# btmat.net
KiCad netlist of a schematic drawn in EAGLE
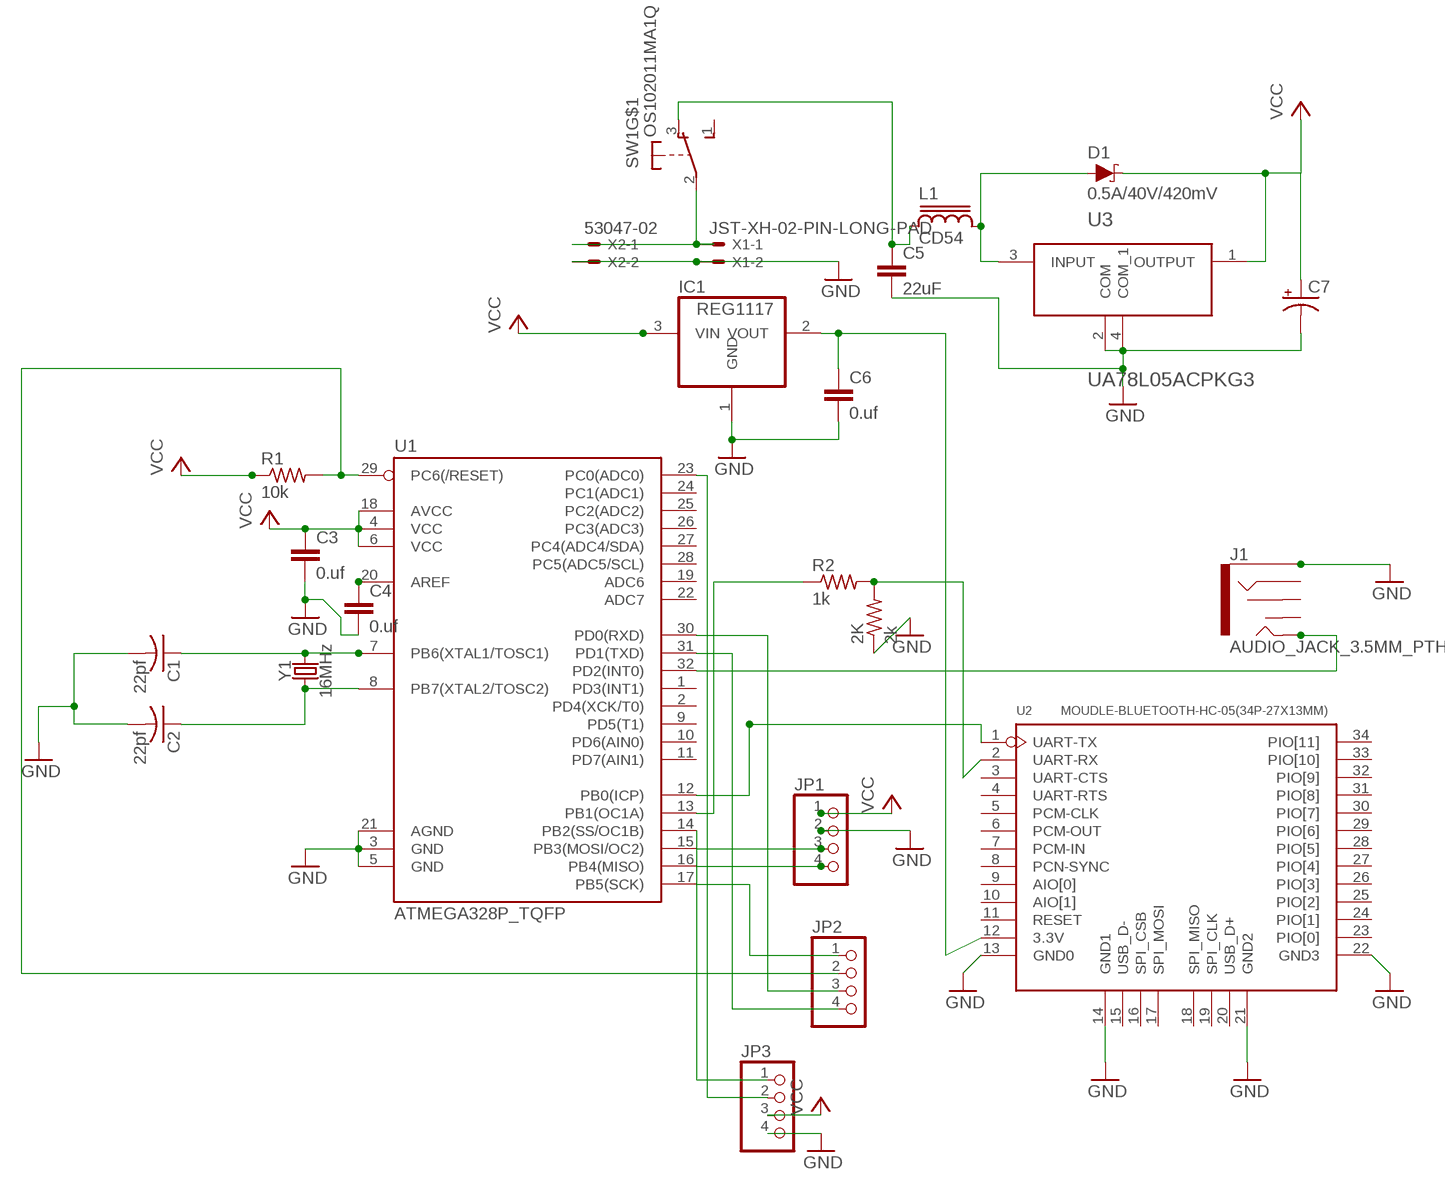
[diagram p0: schematic, sheet 1]

(export (version "E")
  (design (tool "Eeschema 10.0.6"))
  (components
    (comp (ref "2K")
      (value "2k")
      (footprint "eagle-import:R0805")
      (libsource (lib "eagle-import") (part "R-US_R0805"))
    )
    (comp (ref "C1")
      (value "22pf")
      (footprint "eagle-import:C0805")
      (libsource (lib "eagle-import") (part "C-USC0805"))
    )
    (comp (ref "C2")
      (value "22pf")
      (footprint "eagle-import:C0805")
      (libsource (lib "eagle-import") (part "C-USC0805"))
    )
    (comp (ref "C3")
      (value "0.uf")
      (footprint "eagle-import:C0805")
      (libsource (lib "eagle-import") (part "resistor_348_C-EUC0805"))
    )
    (comp (ref "C4")
      (value "0.uf")
      (footprint "eagle-import:C0805")
      (libsource (lib "eagle-import") (part "resistor_348_C-EUC0805"))
    )
    (comp (ref "C5")
      (value "22uF")
      (footprint "eagle-import:C0805")
      (libsource (lib "eagle-import") (part "C-EUC0805"))
    )
    (comp (ref "C6")
      (value "0.uf")
      (footprint "eagle-import:C0805")
      (libsource (lib "eagle-import") (part "resistor_348_C-EUC0805"))
    )
    (comp (ref "C7")
      (value "CPOL-USC/6032-28R")
      (footprint "eagle-import:C_6032-28R")
      (libsource (lib "eagle-import") (part "CPOL-USC/6032-28R"))
    )
    (comp (ref "D1")
      (value "0.5A/40V/420mV")
      (footprint "eagle-import:SOD-323")
      (libsource (lib "eagle-import") (part "DIODE-SCHOTTKY-PMEG4005EJ"))
    )
    (comp (ref "IC1")
      (value "REG1117")
      (footprint "eagle-import:SOT223")
      (libsource (lib "eagle-import") (part "REG1117"))
    )
    (comp (ref "J1")
      (value "AUDIO_JACK_3.5MM_PTH")
      (footprint "eagle-import:AUDIO-JACK")
      (libsource (lib "eagle-import") (part "AUDIO_JACK_3.5MM_PTH"))
    )
    (comp (ref "JP1")
      (value "PINHD-1X4")
      (footprint "eagle-import:1X04")
      (libsource (lib "eagle-import") (part "PINHD-1X4"))
    )
    (comp (ref "JP2")
      (value "PINHD-1X4")
      (footprint "eagle-import:1X04")
      (libsource (lib "eagle-import") (part "PINHD-1X4"))
    )
    (comp (ref "JP3")
      (value "PINHD-1X4")
      (footprint "eagle-import:1X04")
      (libsource (lib "eagle-import") (part "PINHD-1X4"))
    )
    (comp (ref "L1")
      (value "CD54")
      (footprint "eagle-import:CD54")
      (libsource (lib "eagle-import") (part "CD54"))
    )
    (comp (ref "R1")
      (value "10k")
      (footprint "eagle-import:R0805")
      (libsource (lib "eagle-import") (part "R-US_R0805"))
    )
    (comp (ref "R2")
      (value "1k")
      (footprint "eagle-import:R0805")
      (libsource (lib "eagle-import") (part "R-US_R0805"))
    )
    (comp (ref "SW1")
      (value "OS102011MA1Q")
      (footprint "eagle-import:OS102011MA1Q")
      (libsource (lib "eagle-import") (part "OS102011MA1Q"))
    )
    (comp (ref "U1")
      (value "ATMEGA328P_TQFP")
      (footprint "eagle-import:TQFP32-08")
      (libsource (lib "eagle-import") (part "ATMEGA328P_TQFP"))
    )
    (comp (ref "U2")
      (value "MOUDLE-BLUETOOTH-HC-05(34P-27X13MM)")
      (footprint "eagle-import:BT34P-SMD-1.5-26.9X13.0X2.2MM")
      (fields (field (name "MP") "HC-05"))
      (libsource (lib "eagle-import") (part "MOUDLE-BLUETOOTH-HC-05(34P-27X13MM)"))
    )
    (comp (ref "U3")
      (value "UA78L05ACPKG3")
      (footprint "eagle-import:SOT150P400X160-4N")
      (libsource (lib "eagle-import") (part "UA78L05ACPKG3"))
    )
    (comp (ref "X1")
      (value "JST-XH-02-PIN-LONG-PAD")
      (footprint "eagle-import:JST-XH-02-PACKAGE-LONG-PAD")
      (libsource (lib "eagle-import") (part "JST-XH-02-PIN-LONG-PAD"))
    )
    (comp (ref "X2")
      (value "53047-02")
      (footprint "eagle-import:53047-02")
      (fields (field (name "MF") "MOLEX") (field (name "MPN") "53047-0210"))
      (libsource (lib "eagle-import") (part "53?-02047"))
    )
    (comp (ref "Y1")
      (value "16MHz")
      (footprint "eagle-import:HC49US")
      (libsource (lib "eagle-import") (part "CRYSTAL-16MHZPTH-HC49US"))
    )
  )
  (nets
    (net (code "1") (name "GND") (class "Default")
      (node (ref "2K") (pin "1") (pinfunction "1_1") (pintype "passive"))
      (node (ref "C1") (pin "2") (pinfunction "2_2") (pintype "passive"))
      (node (ref "C2") (pin "2") (pinfunction "2_2") (pintype "passive"))
      (node (ref "C3") (pin "2") (pinfunction "2_2") (pintype "passive"))
      (node (ref "C4") (pin "2") (pinfunction "2_2") (pintype "passive"))
      (node (ref "C5") (pin "2") (pinfunction "2_2") (pintype "passive"))
      (node (ref "C6") (pin "2") (pinfunction "2_2") (pintype "passive"))
      (node (ref "C7") (pin "-") (pinfunction "-_-") (pintype "passive"))
      (node (ref "IC1") (pin "1") (pinfunction "GND_1") (pintype "power_in"))
      (node (ref "J1") (pin "SLEEVE") (pinfunction "SLEEVE_SLEEVE") (pintype "bidirectional"))
      (node (ref "JP1") (pin "2") (pinfunction "2_2") (pintype "passive"))
      (node (ref "JP3") (pin "4") (pinfunction "4_4") (pintype "passive"))
      (node (ref "U1") (pin "21") (pinfunction "AGND_21") (pintype "bidirectional"))
      (node (ref "U1") (pin "3") (pinfunction "GND_3") (pintype "bidirectional"))
      (node (ref "U1") (pin "5") (pinfunction "GND_5") (pintype "bidirectional"))
      (node (ref "U2") (pin "13") (pinfunction "GND0_13") (pintype "bidirectional"))
      (node (ref "U2") (pin "14") (pinfunction "GND1_14") (pintype "bidirectional"))
      (node (ref "U2") (pin "21") (pinfunction "GND2_21") (pintype "bidirectional"))
      (node (ref "U2") (pin "22") (pinfunction "GND3_22") (pintype "bidirectional"))
      (node (ref "U3") (pin "2") (pinfunction "COM_2") (pintype "power_in"))
      (node (ref "U3") (pin "4") (pinfunction "COM_1_4") (pintype "power_in"))
      (node (ref "X1") (pin "2") (pinfunction "S_2") (pintype "passive"))
      (node (ref "X2") (pin "2") (pinfunction "S_2") (pintype "passive"))
    )
    (net (code "2") (name "Net-(IC1-VOUT)") (class "Default")
      (node (ref "C6") (pin "1") (pinfunction "1_1") (pintype "passive"))
      (node (ref "IC1") (pin "2") (pinfunction "VOUT_2") (pintype "output"))
      (node (ref "U2") (pin "12") (pinfunction "3.3V_12") (pintype "bidirectional"))
    )
    (net (code "3") (name "Net-(SW1A-O)") (class "Default")
      (node (ref "C5") (pin "1") (pinfunction "1_1") (pintype "passive"))
      (node (ref "L1") (pin "1") (pinfunction "1_1") (pintype "passive"))
      (node (ref "SW1") (pin "3") (pinfunction "O_3") (pintype "passive"))
    )
    (net (code "4") (name "Net-(SW1A-P)") (class "Default")
      (node (ref "SW1") (pin "2") (pinfunction "P_2") (pintype "passive"))
      (node (ref "X1") (pin "1") (pinfunction "S_1") (pintype "passive"))
      (node (ref "X2") (pin "1") (pinfunction "S_1") (pintype "passive"))
    )
    (net (code "5") (name "Net-(U1-AREF)") (class "Default")
      (node (ref "C4") (pin "1") (pinfunction "1_1") (pintype "passive"))
      (node (ref "U1") (pin "20") (pinfunction "AREF_20") (pintype "bidirectional"))
    )
    (net (code "6") (name "Net-(U1-PB0(ICP))") (class "Default")
      (node (ref "U1") (pin "12") (pinfunction "PB0(ICP)_12") (pintype "bidirectional"))
      (node (ref "U2") (pin "1") (pinfunction "UART-TX_1") (pintype "bidirectional"))
    )
    (net (code "7") (name "Net-(U1-PB1(OC1A))") (class "Default")
      (node (ref "R2") (pin "1") (pinfunction "1_1") (pintype "passive"))
      (node (ref "U1") (pin "13") (pinfunction "PB1(OC1A)_13") (pintype "bidirectional"))
    )
    (net (code "8") (name "Net-(U1-PB2(SS{slash}OC1B))") (class "Default")
      (node (ref "JP3") (pin "1") (pinfunction "1_1") (pintype "passive"))
      (node (ref "U1") (pin "14") (pinfunction "PB2(SS/OC1B)_14") (pintype "bidirectional"))
    )
    (net (code "9") (name "Net-(U1-PB3(MOSI{slash}OC2))") (class "Default")
      (node (ref "JP1") (pin "3") (pinfunction "3_3") (pintype "passive"))
      (node (ref "U1") (pin "15") (pinfunction "PB3(MOSI/OC2)_15") (pintype "bidirectional"))
    )
    (net (code "10") (name "Net-(U1-PB4(MISO))") (class "Default")
      (node (ref "JP1") (pin "4") (pinfunction "4_4") (pintype "passive"))
      (node (ref "U1") (pin "16") (pinfunction "PB4(MISO)_16") (pintype "bidirectional"))
    )
    (net (code "11") (name "Net-(U1-PB5(SCK))") (class "Default")
      (node (ref "JP2") (pin "1") (pinfunction "1_1") (pintype "passive"))
      (node (ref "U1") (pin "17") (pinfunction "PB5(SCK)_17") (pintype "bidirectional"))
    )
    (net (code "12") (name "Net-(U1-PB6(XTAL1{slash}TOSC1))") (class "Default")
      (node (ref "C1") (pin "1") (pinfunction "1_1") (pintype "passive"))
      (node (ref "U1") (pin "7") (pinfunction "PB6(XTAL1/TOSC1)_7") (pintype "bidirectional"))
      (node (ref "Y1") (pin "2") (pinfunction "2_2") (pintype "passive"))
    )
    (net (code "13") (name "Net-(U1-PB7(XTAL2{slash}TOSC2))") (class "Default")
      (node (ref "C2") (pin "1") (pinfunction "1_1") (pintype "passive"))
      (node (ref "U1") (pin "8") (pinfunction "PB7(XTAL2/TOSC2)_8") (pintype "bidirectional"))
      (node (ref "Y1") (pin "1") (pinfunction "1_1") (pintype "passive"))
    )
    (net (code "14") (name "Net-(U1-PC0(ADC0))") (class "Default")
      (node (ref "JP3") (pin "2") (pinfunction "2_2") (pintype "passive"))
      (node (ref "U1") (pin "23") (pinfunction "PC0(ADC0)_23") (pintype "bidirectional"))
    )
    (net (code "15") (name "Net-(U1-PC6({slash}RESET))") (class "Default")
      (node (ref "JP2") (pin "2") (pinfunction "2_2") (pintype "passive"))
      (node (ref "R1") (pin "2") (pinfunction "2_2") (pintype "passive"))
      (node (ref "U1") (pin "29") (pinfunction "PC6(/RESET)_29") (pintype "bidirectional"))
    )
    (net (code "16") (name "Net-(U1-PD0(RXD))") (class "Default")
      (node (ref "JP2") (pin "3") (pinfunction "3_3") (pintype "passive"))
      (node (ref "U1") (pin "30") (pinfunction "PD0(RXD)_30") (pintype "bidirectional"))
    )
    (net (code "17") (name "Net-(U1-PD1(TXD))") (class "Default")
      (node (ref "JP2") (pin "4") (pinfunction "4_4") (pintype "passive"))
      (node (ref "U1") (pin "31") (pinfunction "PD1(TXD)_31") (pintype "bidirectional"))
    )
    (net (code "18") (name "Net-(U1-PD2(INT0))") (class "Default")
      (node (ref "J1") (pin "TIP") (pinfunction "TIP_TIP") (pintype "bidirectional"))
      (node (ref "U1") (pin "32") (pinfunction "PD2(INT0)_32") (pintype "bidirectional"))
    )
    (net (code "19") (name "Net-(U2-UART-RX)") (class "Default")
      (node (ref "2K") (pin "2") (pinfunction "2_2") (pintype "passive"))
      (node (ref "R2") (pin "2") (pinfunction "2_2") (pintype "passive"))
      (node (ref "U2") (pin "2") (pinfunction "UART-RX_2") (pintype "bidirectional"))
    )
    (net (code "20") (name "Net-(U3-INPUT)") (class "Default")
      (node (ref "D1") (pin "A") (pinfunction "A_A") (pintype "passive"))
      (node (ref "L1") (pin "2") (pinfunction "2_2") (pintype "passive"))
      (node (ref "U3") (pin "3") (pinfunction "INPUT_3") (pintype "input"))
    )
    (net (code "21") (name "VCC") (class "Default")
      (node (ref "C3") (pin "1") (pinfunction "1_1") (pintype "passive"))
      (node (ref "C7") (pin "+") (pinfunction "+_+") (pintype "passive"))
      (node (ref "D1") (pin "C") (pinfunction "C_C") (pintype "passive"))
      (node (ref "IC1") (pin "3") (pinfunction "VIN_3") (pintype "input"))
      (node (ref "JP1") (pin "1") (pinfunction "1_1") (pintype "passive"))
      (node (ref "JP3") (pin "3") (pinfunction "3_3") (pintype "passive"))
      (node (ref "R1") (pin "1") (pinfunction "1_1") (pintype "passive"))
      (node (ref "U1") (pin "18") (pinfunction "AVCC_18") (pintype "bidirectional"))
      (node (ref "U1") (pin "4") (pinfunction "VCC_4") (pintype "bidirectional"))
      (node (ref "U1") (pin "6") (pinfunction "VCC_6") (pintype "bidirectional"))
      (node (ref "U3") (pin "1") (pinfunction "OUTPUT_1") (pintype "output"))
    )
    (net (code "22") (name "unconnected-(J1-PadRING)") (class "Default")
      (node (ref "J1") (pin "RING") (pinfunction "RING_RING") (pintype "bidirectional"))
    )
    (net (code "23") (name "unconnected-(J1-PadRSH)") (class "Default")
      (node (ref "J1") (pin "RSH") (pinfunction "RSH_RSH") (pintype "bidirectional"))
    )
    (net (code "24") (name "unconnected-(J1-PadTSH)") (class "Default")
      (node (ref "J1") (pin "TSH") (pinfunction "TSH_TSH") (pintype "bidirectional"))
    )
    (net (code "25") (name "unconnected-(SW1A-S-Pad1)") (class "Default")
      (node (ref "SW1") (pin "1") (pinfunction "S_1") (pintype "passive"))
    )
    (net (code "26") (name "unconnected-(U1-ADC6-Pad19)") (class "Default")
      (node (ref "U1") (pin "19") (pinfunction "ADC6_19") (pintype "bidirectional"))
    )
    (net (code "27") (name "unconnected-(U1-ADC7-Pad22)") (class "Default")
      (node (ref "U1") (pin "22") (pinfunction "ADC7_22") (pintype "bidirectional"))
    )
    (net (code "28") (name "unconnected-(U1-PC1(ADC1)-Pad24)") (class "Default")
      (node (ref "U1") (pin "24") (pinfunction "PC1(ADC1)_24") (pintype "bidirectional"))
    )
    (net (code "29") (name "unconnected-(U1-PC2(ADC2)-Pad25)") (class "Default")
      (node (ref "U1") (pin "25") (pinfunction "PC2(ADC2)_25") (pintype "bidirectional"))
    )
    (net (code "30") (name "unconnected-(U1-PC3(ADC3)-Pad26)") (class "Default")
      (node (ref "U1") (pin "26") (pinfunction "PC3(ADC3)_26") (pintype "bidirectional"))
    )
    (net (code "31") (name "unconnected-(U1-PC4(ADC4{slash}SDA)-Pad27)") (class "Default")
      (node (ref "U1") (pin "27") (pinfunction "PC4(ADC4/SDA)_27") (pintype "bidirectional"))
    )
    (net (code "32") (name "unconnected-(U1-PC5(ADC5{slash}SCL)-Pad28)") (class "Default")
      (node (ref "U1") (pin "28") (pinfunction "PC5(ADC5/SCL)_28") (pintype "bidirectional"))
    )
    (net (code "33") (name "unconnected-(U1-PD3(INT1)-Pad1)") (class "Default")
      (node (ref "U1") (pin "1") (pinfunction "PD3(INT1)_1") (pintype "bidirectional"))
    )
    (net (code "34") (name "unconnected-(U1-PD4(XCK{slash}T0)-Pad2)") (class "Default")
      (node (ref "U1") (pin "2") (pinfunction "PD4(XCK/T0)_2") (pintype "bidirectional"))
    )
    (net (code "35") (name "unconnected-(U1-PD5(T1)-Pad9)") (class "Default")
      (node (ref "U1") (pin "9") (pinfunction "PD5(T1)_9") (pintype "bidirectional"))
    )
    (net (code "36") (name "unconnected-(U1-PD6(AIN0)-Pad10)") (class "Default")
      (node (ref "U1") (pin "10") (pinfunction "PD6(AIN0)_10") (pintype "bidirectional"))
    )
    (net (code "37") (name "unconnected-(U1-PD7(AIN1)-Pad11)") (class "Default")
      (node (ref "U1") (pin "11") (pinfunction "PD7(AIN1)_11") (pintype "bidirectional"))
    )
    (net (code "38") (name "unconnected-(U2-AIO[0]-Pad9)") (class "Default")
      (node (ref "U2") (pin "9") (pinfunction "AIO[0]_9") (pintype "bidirectional"))
    )
    (net (code "39") (name "unconnected-(U2-AIO[1]-Pad10)") (class "Default")
      (node (ref "U2") (pin "10") (pinfunction "AIO[1]_10") (pintype "bidirectional"))
    )
    (net (code "40") (name "unconnected-(U2-PCM-CLK-Pad5)") (class "Default")
      (node (ref "U2") (pin "5") (pinfunction "PCM-CLK_5") (pintype "bidirectional"))
    )
    (net (code "41") (name "unconnected-(U2-PCM-IN-Pad7)") (class "Default")
      (node (ref "U2") (pin "7") (pinfunction "PCM-IN_7") (pintype "bidirectional"))
    )
    (net (code "42") (name "unconnected-(U2-PCM-OUT-Pad6)") (class "Default")
      (node (ref "U2") (pin "6") (pinfunction "PCM-OUT_6") (pintype "bidirectional"))
    )
    (net (code "43") (name "unconnected-(U2-PCN-SYNC-Pad8)") (class "Default")
      (node (ref "U2") (pin "8") (pinfunction "PCN-SYNC_8") (pintype "bidirectional"))
    )
    (net (code "44") (name "unconnected-(U2-PIO[0]-Pad23)") (class "Default")
      (node (ref "U2") (pin "23") (pinfunction "PIO[0]_23") (pintype "bidirectional"))
    )
    (net (code "45") (name "unconnected-(U2-PIO[1]-Pad24)") (class "Default")
      (node (ref "U2") (pin "24") (pinfunction "PIO[1]_24") (pintype "bidirectional"))
    )
    (net (code "46") (name "unconnected-(U2-PIO[2]-Pad25)") (class "Default")
      (node (ref "U2") (pin "25") (pinfunction "PIO[2]_25") (pintype "bidirectional"))
    )
    (net (code "47") (name "unconnected-(U2-PIO[3]-Pad26)") (class "Default")
      (node (ref "U2") (pin "26") (pinfunction "PIO[3]_26") (pintype "bidirectional"))
    )
    (net (code "48") (name "unconnected-(U2-PIO[4]-Pad27)") (class "Default")
      (node (ref "U2") (pin "27") (pinfunction "PIO[4]_27") (pintype "bidirectional"))
    )
    (net (code "49") (name "unconnected-(U2-PIO[5]-Pad28)") (class "Default")
      (node (ref "U2") (pin "28") (pinfunction "PIO[5]_28") (pintype "bidirectional"))
    )
    (net (code "50") (name "unconnected-(U2-PIO[6]-Pad29)") (class "Default")
      (node (ref "U2") (pin "29") (pinfunction "PIO[6]_29") (pintype "bidirectional"))
    )
    (net (code "51") (name "unconnected-(U2-PIO[7]-Pad30)") (class "Default")
      (node (ref "U2") (pin "30") (pinfunction "PIO[7]_30") (pintype "bidirectional"))
    )
    (net (code "52") (name "unconnected-(U2-PIO[8]-Pad31)") (class "Default")
      (node (ref "U2") (pin "31") (pinfunction "PIO[8]_31") (pintype "bidirectional"))
    )
    (net (code "53") (name "unconnected-(U2-PIO[9]-Pad32)") (class "Default")
      (node (ref "U2") (pin "32") (pinfunction "PIO[9]_32") (pintype "bidirectional"))
    )
    (net (code "54") (name "unconnected-(U2-PIO[10]-Pad33)") (class "Default")
      (node (ref "U2") (pin "33") (pinfunction "PIO[10]_33") (pintype "bidirectional"))
    )
    (net (code "55") (name "unconnected-(U2-PIO[11]-Pad34)") (class "Default")
      (node (ref "U2") (pin "34") (pinfunction "PIO[11]_34") (pintype "bidirectional"))
    )
    (net (code "56") (name "unconnected-(U2-RESET-Pad11)") (class "Default")
      (node (ref "U2") (pin "11") (pinfunction "RESET_11") (pintype "bidirectional"))
    )
    (net (code "57") (name "unconnected-(U2-SPI_CLK-Pad19)") (class "Default")
      (node (ref "U2") (pin "19") (pinfunction "SPI_CLK_19") (pintype "bidirectional"))
    )
    (net (code "58") (name "unconnected-(U2-SPI_CSB-Pad16)") (class "Default")
      (node (ref "U2") (pin "16") (pinfunction "SPI_CSB_16") (pintype "bidirectional"))
    )
    (net (code "59") (name "unconnected-(U2-SPI_MISO-Pad18)") (class "Default")
      (node (ref "U2") (pin "18") (pinfunction "SPI_MISO_18") (pintype "bidirectional"))
    )
    (net (code "60") (name "unconnected-(U2-SPI_MOSI-Pad17)") (class "Default")
      (node (ref "U2") (pin "17") (pinfunction "SPI_MOSI_17") (pintype "bidirectional"))
    )
    (net (code "61") (name "unconnected-(U2-UART-CTS-Pad3)") (class "Default")
      (node (ref "U2") (pin "3") (pinfunction "UART-CTS_3") (pintype "bidirectional"))
    )
    (net (code "62") (name "unconnected-(U2-UART-RTS-Pad4)") (class "Default")
      (node (ref "U2") (pin "4") (pinfunction "UART-RTS_4") (pintype "bidirectional"))
    )
    (net (code "63") (name "unconnected-(U2-USB_D+-Pad20)") (class "Default")
      (node (ref "U2") (pin "20") (pinfunction "USB_D+_20") (pintype "bidirectional"))
    )
    (net (code "64") (name "unconnected-(U2-USB_D--Pad15)") (class "Default")
      (node (ref "U2") (pin "15") (pinfunction "USB_D-_15") (pintype "bidirectional"))
    )
  )
)
